# ascender_board.net
KiCad netlist of a schematic drawn in EAGLE
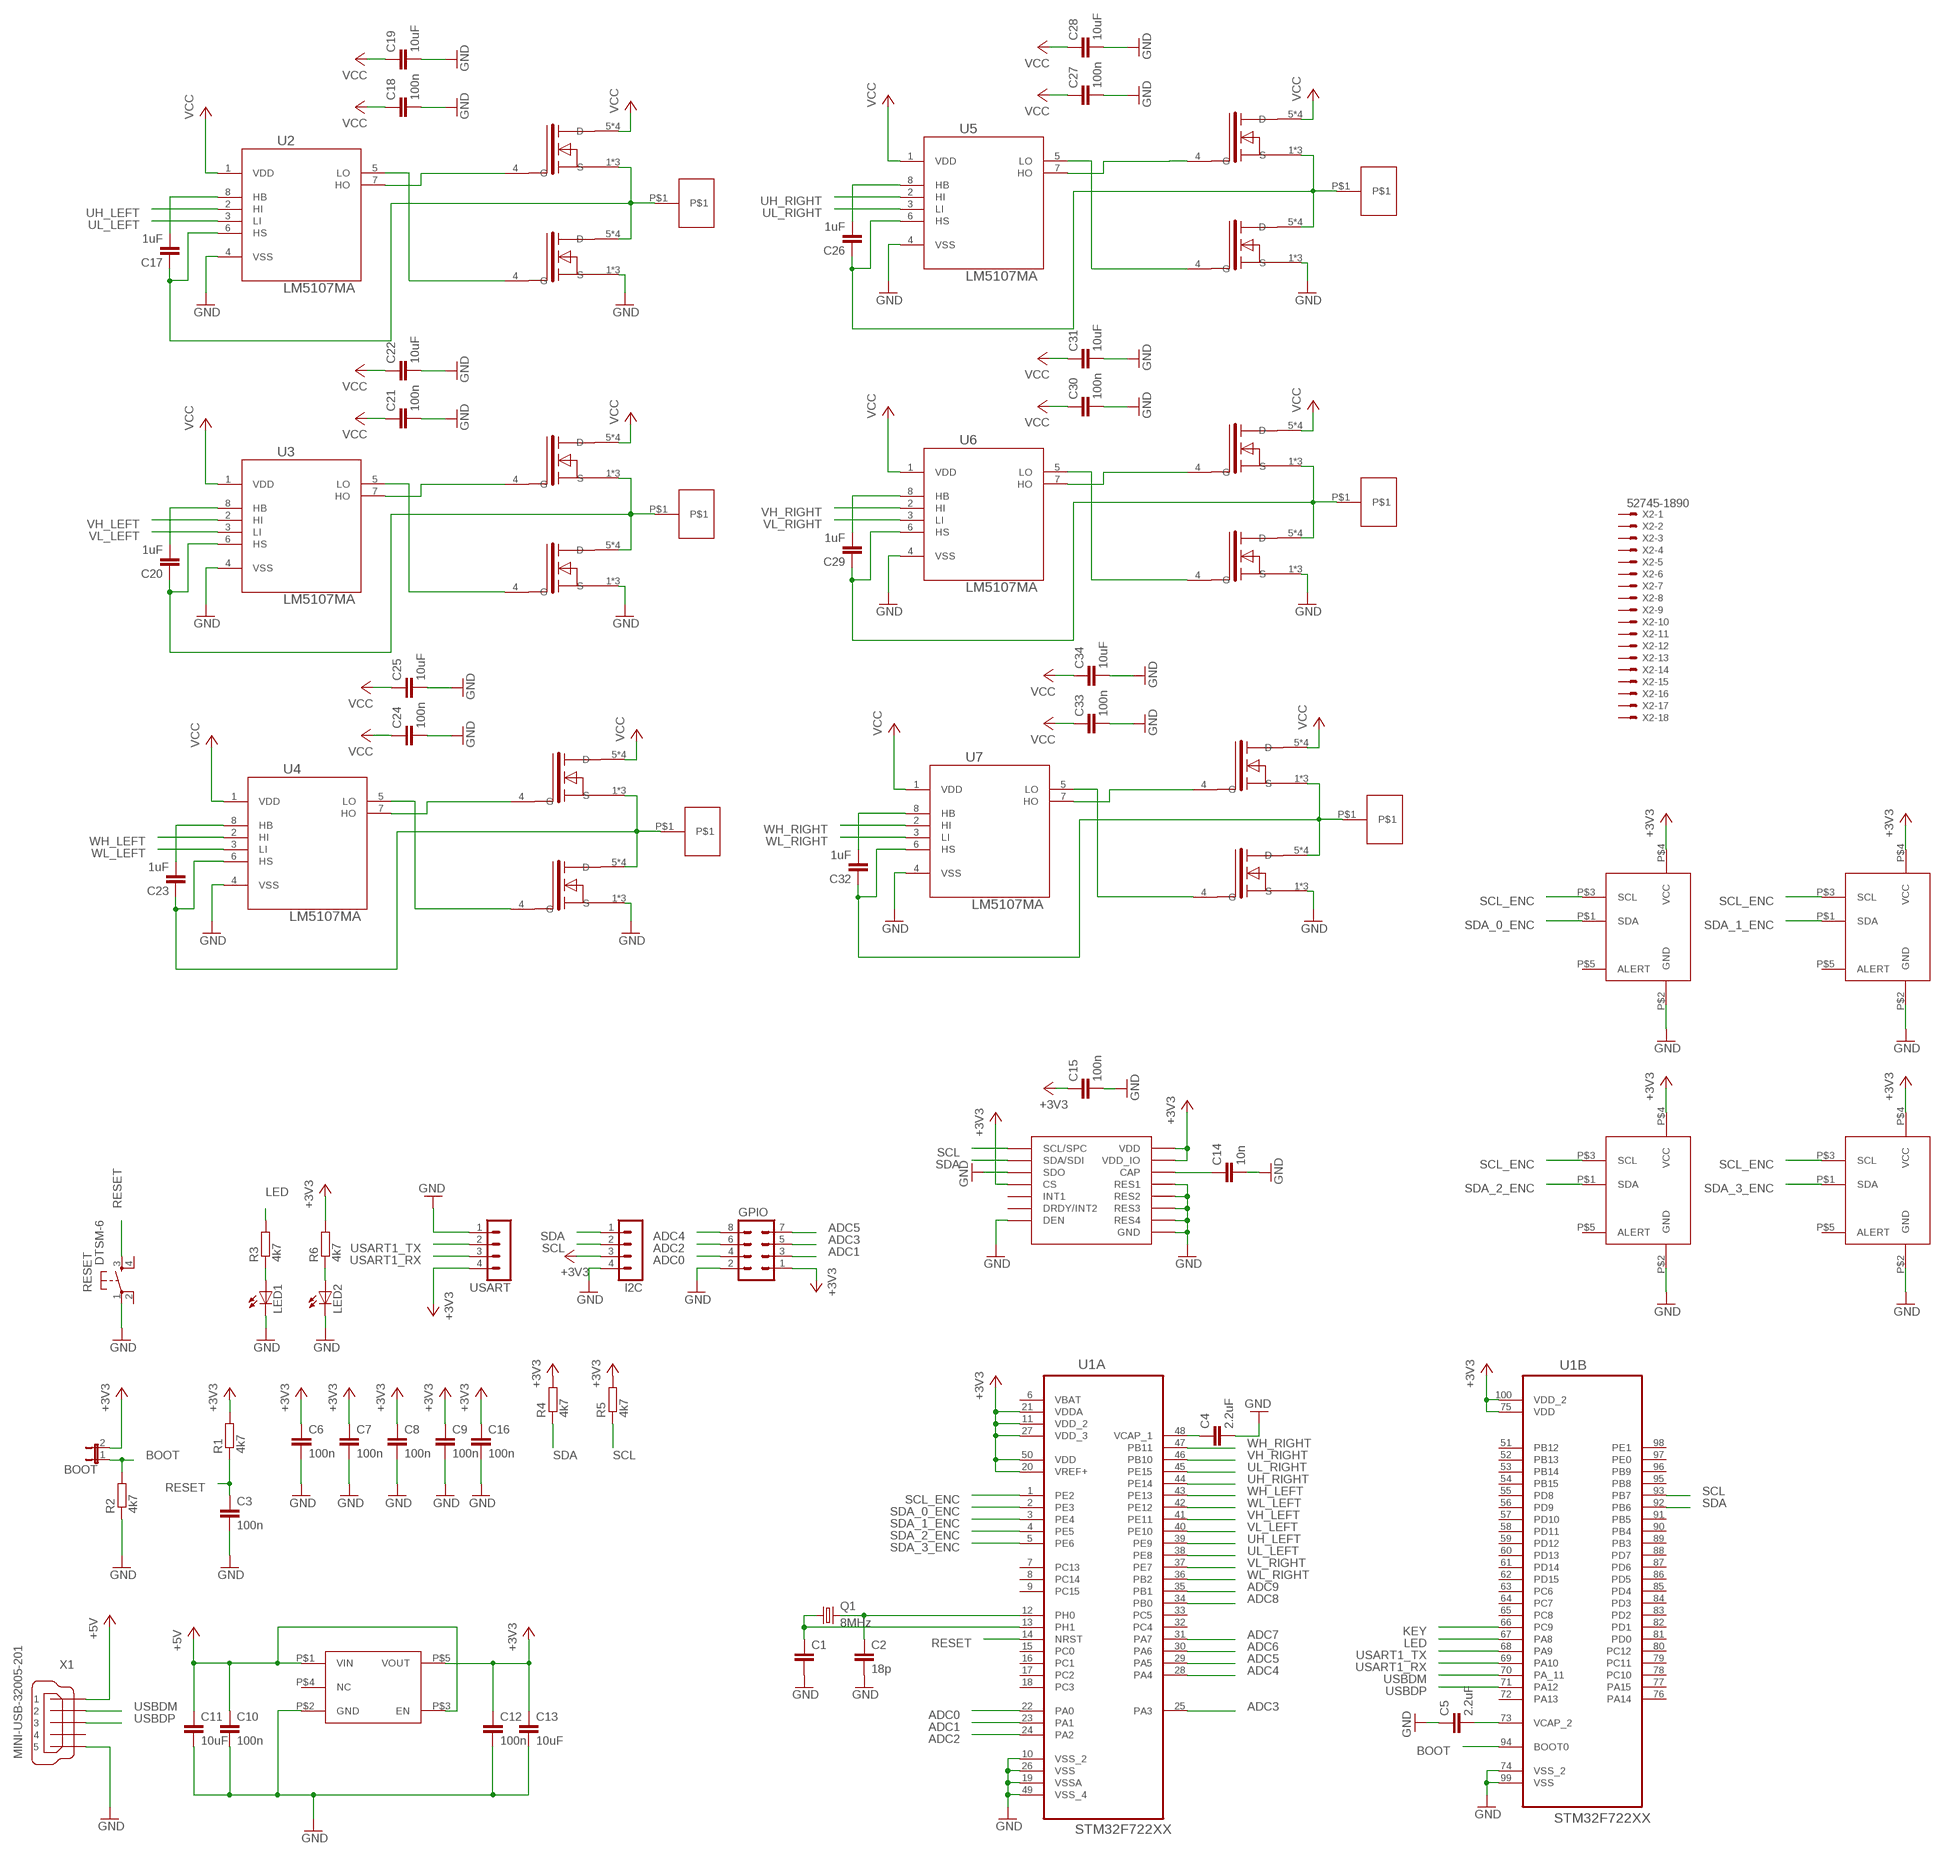
[diagram p0: schematic, sheet 1]

(export (version "E")
  (design (tool "Eeschema 10.0.6"))
  (components
    (comp (ref "BOOT")
      (value "JP1E")
      (footprint "eagle-import:JP1")
      (libsource (lib "eagle-import") (part "JP1E"))
    )
    (comp (ref "C1")
      (value "C-EUC0805")
      (footprint "eagle-import:C0805")
      (libsource (lib "eagle-import") (part "C-EUC0805"))
    )
    (comp (ref "C2")
      (value "18p")
      (footprint "eagle-import:C0805")
      (libsource (lib "eagle-import") (part "C-EUC0805"))
    )
    (comp (ref "C3")
      (value "100n")
      (footprint "eagle-import:C0805")
      (libsource (lib "eagle-import") (part "C-EUC0805"))
    )
    (comp (ref "C4")
      (value "2.2uF")
      (footprint "eagle-import:C0805")
      (libsource (lib "eagle-import") (part "C-EUC0805"))
    )
    (comp (ref "C5")
      (value "2.2uF")
      (footprint "eagle-import:C0805")
      (libsource (lib "eagle-import") (part "C-EUC0805"))
    )
    (comp (ref "C6")
      (value "100n")
      (footprint "eagle-import:C0805")
      (libsource (lib "eagle-import") (part "C-EUC0805"))
    )
    (comp (ref "C7")
      (value "100n")
      (footprint "eagle-import:C0805")
      (libsource (lib "eagle-import") (part "C-EUC0805"))
    )
    (comp (ref "C8")
      (value "100n")
      (footprint "eagle-import:C0805")
      (libsource (lib "eagle-import") (part "C-EUC0805"))
    )
    (comp (ref "C9")
      (value "100n")
      (footprint "eagle-import:C0805")
      (libsource (lib "eagle-import") (part "C-EUC0805"))
    )
    (comp (ref "C10")
      (value "100n")
      (footprint "eagle-import:C0805")
      (libsource (lib "eagle-import") (part "C-EUC0805"))
    )
    (comp (ref "C11")
      (value "10uF")
      (footprint "eagle-import:C0805")
      (libsource (lib "eagle-import") (part "C-EUC0805"))
    )
    (comp (ref "C12")
      (value "100n")
      (footprint "eagle-import:C0805")
      (libsource (lib "eagle-import") (part "C-EUC0805"))
    )
    (comp (ref "C13")
      (value "10uF")
      (footprint "eagle-import:C0805")
      (libsource (lib "eagle-import") (part "C-EUC0805"))
    )
    (comp (ref "C14")
      (value "10n")
      (footprint "eagle-import:C0805")
      (libsource (lib "eagle-import") (part "C-EUC0805"))
    )
    (comp (ref "C15")
      (value "100n")
      (footprint "eagle-import:C0805")
      (libsource (lib "eagle-import") (part "C-EUC0805"))
    )
    (comp (ref "C16")
      (value "100n")
      (footprint "eagle-import:C0805")
      (libsource (lib "eagle-import") (part "C-EUC0805"))
    )
    (comp (ref "C17")
      (value "1uF")
      (footprint "eagle-import:C0805")
      (libsource (lib "eagle-import") (part "C-EUC0805"))
    )
    (comp (ref "C18")
      (value "100n")
      (footprint "eagle-import:C0805")
      (libsource (lib "eagle-import") (part "C-EUC0805"))
    )
    (comp (ref "C19")
      (value "10uF")
      (footprint "eagle-import:C0805")
      (libsource (lib "eagle-import") (part "C-EUC0805"))
    )
    (comp (ref "C20")
      (value "1uF")
      (footprint "eagle-import:C0805")
      (libsource (lib "eagle-import") (part "C-EUC0805"))
    )
    (comp (ref "C21")
      (value "100n")
      (footprint "eagle-import:C0805")
      (libsource (lib "eagle-import") (part "C-EUC0805"))
    )
    (comp (ref "C22")
      (value "10uF")
      (footprint "eagle-import:C0805")
      (libsource (lib "eagle-import") (part "C-EUC0805"))
    )
    (comp (ref "C23")
      (value "1uF")
      (footprint "eagle-import:C0805")
      (libsource (lib "eagle-import") (part "C-EUC0805"))
    )
    (comp (ref "C24")
      (value "100n")
      (footprint "eagle-import:C0805")
      (libsource (lib "eagle-import") (part "C-EUC0805"))
    )
    (comp (ref "C25")
      (value "10uF")
      (footprint "eagle-import:C0805")
      (libsource (lib "eagle-import") (part "C-EUC0805"))
    )
    (comp (ref "C26")
      (value "1uF")
      (footprint "eagle-import:C0805")
      (libsource (lib "eagle-import") (part "C-EUC0805"))
    )
    (comp (ref "C27")
      (value "100n")
      (footprint "eagle-import:C0805")
      (libsource (lib "eagle-import") (part "C-EUC0805"))
    )
    (comp (ref "C28")
      (value "10uF")
      (footprint "eagle-import:C0805")
      (libsource (lib "eagle-import") (part "C-EUC0805"))
    )
    (comp (ref "C29")
      (value "1uF")
      (footprint "eagle-import:C0805")
      (libsource (lib "eagle-import") (part "C-EUC0805"))
    )
    (comp (ref "C30")
      (value "100n")
      (footprint "eagle-import:C0805")
      (libsource (lib "eagle-import") (part "C-EUC0805"))
    )
    (comp (ref "C31")
      (value "10uF")
      (footprint "eagle-import:C0805")
      (libsource (lib "eagle-import") (part "C-EUC0805"))
    )
    (comp (ref "C32")
      (value "1uF")
      (footprint "eagle-import:C0805")
      (libsource (lib "eagle-import") (part "C-EUC0805"))
    )
    (comp (ref "C33")
      (value "100n")
      (footprint "eagle-import:C0805")
      (libsource (lib "eagle-import") (part "C-EUC0805"))
    )
    (comp (ref "C34")
      (value "10uF")
      (footprint "eagle-import:C0805")
      (libsource (lib "eagle-import") (part "C-EUC0805"))
    )
    (comp (ref "GPIO")
      (value "MA04-2")
      (footprint "eagle-import:MA04-2")
      (libsource (lib "eagle-import") (part "MA04-2"))
    )
    (comp (ref "I2C")
      (value "MA04-1")
      (footprint "eagle-import:MA04-1")
      (libsource (lib "eagle-import") (part "MA04-1"))
    )
    (comp (ref "LED1")
      (value "LEDCHIPLED_1206")
      (footprint "eagle-import:CHIPLED_1206")
      (libsource (lib "eagle-import") (part "LEDCHIPLED_1206"))
    )
    (comp (ref "LED2")
      (value "LEDCHIPLED_1206")
      (footprint "eagle-import:CHIPLED_1206")
      (libsource (lib "eagle-import") (part "LEDCHIPLED_1206"))
    )
    (comp (ref "Q1")
      (value "8MHz")
      (footprint "eagle-import:CTS406")
      (libsource (lib "eagle-import") (part "CRYSTALCTS406"))
    )
    (comp (ref "R1")
      (value "4k7")
      (footprint "eagle-import:M0805")
      (libsource (lib "eagle-import") (part "R-EU_M0805"))
    )
    (comp (ref "R2")
      (value "4k7")
      (footprint "eagle-import:M0805")
      (libsource (lib "eagle-import") (part "R-EU_M0805"))
    )
    (comp (ref "R3")
      (value "4k7")
      (footprint "eagle-import:M0805")
      (libsource (lib "eagle-import") (part "R-EU_M0805"))
    )
    (comp (ref "R4")
      (value "4k7")
      (footprint "eagle-import:M0805")
      (libsource (lib "eagle-import") (part "R-EU_M0805"))
    )
    (comp (ref "R5")
      (value "4k7")
      (footprint "eagle-import:M0805")
      (libsource (lib "eagle-import") (part "R-EU_M0805"))
    )
    (comp (ref "R6")
      (value "4k7")
      (footprint "eagle-import:M0805")
      (libsource (lib "eagle-import") (part "R-EU_M0805"))
    )
    (comp (ref "RESET")
      (value "DTSM-6")
      (footprint "eagle-import:DTSM-6")
      (libsource (lib "eagle-import") (part "DTSM-6"))
    )
    (comp (ref "U$1")
      (value "MIC5504-3.3Y")
      (footprint "eagle-import:SOT23-5")
      (libsource (lib "eagle-import") (part "MIC5504-3.3Y"))
    )
    (comp (ref "U$2")
      (value "ST_L3GD20H")
      (footprint "eagle-import:ST_LGA16L")
      (libsource (lib "eagle-import") (part "ST_L3GD20H"))
    )
    (comp (ref "U$4")
      (value "IRFH7004")
      (footprint "eagle-import:PQFN5X6")
      (libsource (lib "eagle-import") (part "IRFH7004"))
    )
    (comp (ref "U$5")
      (value "IRFH7004")
      (footprint "eagle-import:PQFN5X6")
      (libsource (lib "eagle-import") (part "IRFH7004"))
    )
    (comp (ref "U$6")
      (value "BLDC_MOTOR_PIN")
      (footprint "eagle-import:BLDC_MOTOR_PIN")
      (libsource (lib "eagle-import") (part "BLDC_MOTOR_PIN"))
    )
    (comp (ref "U$7")
      (value "IRFH7004")
      (footprint "eagle-import:PQFN5X6")
      (libsource (lib "eagle-import") (part "IRFH7004"))
    )
    (comp (ref "U$8")
      (value "IRFH7004")
      (footprint "eagle-import:PQFN5X6")
      (libsource (lib "eagle-import") (part "IRFH7004"))
    )
    (comp (ref "U$9")
      (value "BLDC_MOTOR_PIN")
      (footprint "eagle-import:BLDC_MOTOR_PIN")
      (libsource (lib "eagle-import") (part "BLDC_MOTOR_PIN"))
    )
    (comp (ref "U$10")
      (value "IRFH7004")
      (footprint "eagle-import:PQFN5X6")
      (libsource (lib "eagle-import") (part "IRFH7004"))
    )
    (comp (ref "U$11")
      (value "IRFH7004")
      (footprint "eagle-import:PQFN5X6")
      (libsource (lib "eagle-import") (part "IRFH7004"))
    )
    (comp (ref "U$12")
      (value "BLDC_MOTOR_PIN")
      (footprint "eagle-import:BLDC_MOTOR_PIN")
      (libsource (lib "eagle-import") (part "BLDC_MOTOR_PIN"))
    )
    (comp (ref "U$13")
      (value "IRFH7004")
      (footprint "eagle-import:PQFN5X6")
      (libsource (lib "eagle-import") (part "IRFH7004"))
    )
    (comp (ref "U$14")
      (value "IRFH7004")
      (footprint "eagle-import:PQFN5X6")
      (libsource (lib "eagle-import") (part "IRFH7004"))
    )
    (comp (ref "U$15")
      (value "BLDC_MOTOR_PIN")
      (footprint "eagle-import:BLDC_MOTOR_PIN")
      (libsource (lib "eagle-import") (part "BLDC_MOTOR_PIN"))
    )
    (comp (ref "U$16")
      (value "IRFH7004")
      (footprint "eagle-import:PQFN5X6")
      (libsource (lib "eagle-import") (part "IRFH7004"))
    )
    (comp (ref "U$17")
      (value "IRFH7004")
      (footprint "eagle-import:PQFN5X6")
      (libsource (lib "eagle-import") (part "IRFH7004"))
    )
    (comp (ref "U$18")
      (value "BLDC_MOTOR_PIN")
      (footprint "eagle-import:BLDC_MOTOR_PIN")
      (libsource (lib "eagle-import") (part "BLDC_MOTOR_PIN"))
    )
    (comp (ref "U$19")
      (value "IRFH7004")
      (footprint "eagle-import:PQFN5X6")
      (libsource (lib "eagle-import") (part "IRFH7004"))
    )
    (comp (ref "U$20")
      (value "IRFH7004")
      (footprint "eagle-import:PQFN5X6")
      (libsource (lib "eagle-import") (part "IRFH7004"))
    )
    (comp (ref "U$21")
      (value "BLDC_MOTOR_PIN")
      (footprint "eagle-import:BLDC_MOTOR_PIN")
      (libsource (lib "eagle-import") (part "BLDC_MOTOR_PIN"))
    )
    (comp (ref "U$22")
      (value "SI7210")
      (footprint "eagle-import:SOT23-5")
      (libsource (lib "eagle-import") (part "SI7210"))
    )
    (comp (ref "U$23")
      (value "SI7210")
      (footprint "eagle-import:SOT23-5")
      (libsource (lib "eagle-import") (part "SI7210"))
    )
    (comp (ref "U$24")
      (value "SI7210")
      (footprint "eagle-import:SOT23-5")
      (libsource (lib "eagle-import") (part "SI7210"))
    )
    (comp (ref "U$25")
      (value "SI7210")
      (footprint "eagle-import:SOT23-5")
      (libsource (lib "eagle-import") (part "SI7210"))
    )
    (comp (ref "U1")
      (value "STM32F722XX")
      (footprint "eagle-import:QFP50P1600X1600X160-100N")
      (fields (field (name "MPN") "STM32F407VET6"))
      (libsource (lib "eagle-import") (part "STM32F722XX"))
    )
    (comp (ref "U2")
      (value "LM5107MA")
      (footprint "eagle-import:SOIC127P620X175-8N")
      (libsource (lib "eagle-import") (part "LM5107MA"))
    )
    (comp (ref "U3")
      (value "LM5107MA")
      (footprint "eagle-import:SOIC127P620X175-8N")
      (libsource (lib "eagle-import") (part "LM5107MA"))
    )
    (comp (ref "U4")
      (value "LM5107MA")
      (footprint "eagle-import:SOIC127P620X175-8N")
      (libsource (lib "eagle-import") (part "LM5107MA"))
    )
    (comp (ref "U5")
      (value "LM5107MA")
      (footprint "eagle-import:SOIC127P620X175-8N")
      (libsource (lib "eagle-import") (part "LM5107MA"))
    )
    (comp (ref "U6")
      (value "LM5107MA")
      (footprint "eagle-import:SOIC127P620X175-8N")
      (libsource (lib "eagle-import") (part "LM5107MA"))
    )
    (comp (ref "U7")
      (value "LM5107MA")
      (footprint "eagle-import:SOIC127P620X175-8N")
      (libsource (lib "eagle-import") (part "LM5107MA"))
    )
    (comp (ref "USART")
      (value "MA04-1")
      (footprint "eagle-import:MA04-1")
      (libsource (lib "eagle-import") (part "MA04-1"))
    )
    (comp (ref "X1")
      (value "MINI-USB-32005-201")
      (footprint "eagle-import:32005-201")
      (libsource (lib "eagle-import") (part "MINI-USB-32005-201"))
    )
    (comp (ref "X2")
      (value "52745-1890")
      (footprint "eagle-import:52745-1890")
      (libsource (lib "eagle-import") (part "52745-1890"))
    )
  )
  (nets
    (net (code "1") (name "+3V3") (class "Default")
      (node (ref "BOOT") (pin "2") (pinfunction "2_2") (pintype "passive"))
      (node (ref "C12") (pin "1") (pinfunction "1_1") (pintype "passive"))
      (node (ref "C13") (pin "1") (pinfunction "1_1") (pintype "passive"))
      (node (ref "C15") (pin "1") (pinfunction "1_1") (pintype "passive"))
      (node (ref "C16") (pin "1") (pinfunction "1_1") (pintype "passive"))
      (node (ref "C6") (pin "1") (pinfunction "1_1") (pintype "passive"))
      (node (ref "C7") (pin "1") (pinfunction "1_1") (pintype "passive"))
      (node (ref "C8") (pin "1") (pinfunction "1_1") (pintype "passive"))
      (node (ref "C9") (pin "1") (pinfunction "1_1") (pintype "passive"))
      (node (ref "GPIO") (pin "1") (pinfunction "1_1") (pintype "passive"))
      (node (ref "I2C") (pin "3") (pinfunction "3_3") (pintype "passive"))
      (node (ref "R1") (pin "2") (pinfunction "2_2") (pintype "passive"))
      (node (ref "R4") (pin "2") (pinfunction "2_2") (pintype "passive"))
      (node (ref "R5") (pin "2") (pinfunction "2_2") (pintype "passive"))
      (node (ref "R6") (pin "2") (pinfunction "2_2") (pintype "passive"))
      (node (ref "U$1") (pin "P$5") (pinfunction "VOUT_P$5") (pintype "bidirectional"))
      (node (ref "U$2") (pin "P$1") (pinfunction "VDD_IO_P$1") (pintype "power_in"))
      (node (ref "U$2") (pin "P$16") (pinfunction "VDD_P$16") (pintype "power_in"))
      (node (ref "U$2") (pin "P$5") (pinfunction "CS_P$5") (pintype "bidirectional"))
      (node (ref "U$22") (pin "P$4") (pinfunction "VCC_P$4") (pintype "bidirectional"))
      (node (ref "U$23") (pin "P$4") (pinfunction "VCC_P$4") (pintype "bidirectional"))
      (node (ref "U$24") (pin "P$4") (pinfunction "VCC_P$4") (pintype "bidirectional"))
      (node (ref "U$25") (pin "P$4") (pinfunction "VCC_P$4") (pintype "bidirectional"))
      (node (ref "U1") (pin "100") (pinfunction "VDD_2_100") (pintype "power_in"))
      (node (ref "U1") (pin "11") (pinfunction "VDD_2_11") (pintype "power_in"))
      (node (ref "U1") (pin "20") (pinfunction "VREF+_20") (pintype "power_in"))
      (node (ref "U1") (pin "21") (pinfunction "VDDA_21") (pintype "power_in"))
      (node (ref "U1") (pin "27") (pinfunction "VDD_3_27") (pintype "power_in"))
      (node (ref "U1") (pin "50") (pinfunction "VDD_50") (pintype "power_in"))
      (node (ref "U1") (pin "75") (pinfunction "VDD_75") (pintype "power_in"))
      (node (ref "USART") (pin "4") (pinfunction "4_4") (pintype "passive"))
    )
    (net (code "2") (name "+5V") (class "Default")
      (node (ref "C10") (pin "1") (pinfunction "1_1") (pintype "passive"))
      (node (ref "C11") (pin "1") (pinfunction "1_1") (pintype "passive"))
      (node (ref "U$1") (pin "P$1") (pinfunction "VIN_P$1") (pintype "bidirectional"))
      (node (ref "U$1") (pin "P$3") (pinfunction "EN_P$3") (pintype "bidirectional"))
      (node (ref "X1") (pin "1") (pinfunction "1_1") (pintype "passive"))
    )
    (net (code "3") (name "/ADC0") (class "Default")
      (node (ref "GPIO") (pin "4") (pinfunction "4_4") (pintype "passive"))
      (node (ref "U1") (pin "22") (pinfunction "PA0_22") (pintype "bidirectional"))
    )
    (net (code "4") (name "/ADC1") (class "Default")
      (node (ref "GPIO") (pin "3") (pinfunction "3_3") (pintype "passive"))
      (node (ref "U1") (pin "23") (pinfunction "PA1_23") (pintype "bidirectional"))
    )
    (net (code "5") (name "/ADC2") (class "Default")
      (node (ref "GPIO") (pin "6") (pinfunction "6_6") (pintype "passive"))
      (node (ref "U1") (pin "24") (pinfunction "PA2_24") (pintype "bidirectional"))
    )
    (net (code "6") (name "/ADC3") (class "Default")
      (node (ref "GPIO") (pin "5") (pinfunction "5_5") (pintype "passive"))
      (node (ref "U1") (pin "25") (pinfunction "PA3_25") (pintype "bidirectional"))
    )
    (net (code "7") (name "/ADC4") (class "Default")
      (node (ref "GPIO") (pin "8") (pinfunction "8_8") (pintype "passive"))
      (node (ref "U1") (pin "28") (pinfunction "PA4_28") (pintype "bidirectional"))
    )
    (net (code "8") (name "/ADC5") (class "Default")
      (node (ref "GPIO") (pin "7") (pinfunction "7_7") (pintype "passive"))
      (node (ref "U1") (pin "29") (pinfunction "PA5_29") (pintype "bidirectional"))
    )
    (net (code "9") (name "/ADC6") (class "Default")
      (node (ref "U1") (pin "30") (pinfunction "PA6_30") (pintype "bidirectional"))
    )
    (net (code "10") (name "/ADC7") (class "Default")
      (node (ref "U1") (pin "31") (pinfunction "PA7_31") (pintype "bidirectional"))
    )
    (net (code "11") (name "/ADC8") (class "Default")
      (node (ref "U1") (pin "34") (pinfunction "PB0_34") (pintype "bidirectional"))
    )
    (net (code "12") (name "/ADC9") (class "Default")
      (node (ref "U1") (pin "35") (pinfunction "PB1_35") (pintype "bidirectional"))
    )
    (net (code "13") (name "/BOOT") (class "Default")
      (node (ref "BOOT") (pin "1") (pinfunction "1_1") (pintype "passive"))
      (node (ref "R2") (pin "2") (pinfunction "2_2") (pintype "passive"))
      (node (ref "U1") (pin "94") (pinfunction "BOOT0_94") (pintype "input"))
    )
    (net (code "14") (name "/KEY") (class "Default")
      (node (ref "U1") (pin "66") (pinfunction "PC9_66") (pintype "bidirectional"))
    )
    (net (code "15") (name "/LED") (class "Default")
      (node (ref "R3") (pin "2") (pinfunction "2_2") (pintype "passive"))
      (node (ref "U1") (pin "67") (pinfunction "PA8_67") (pintype "bidirectional"))
    )
    (net (code "16") (name "/RESET") (class "Default")
      (node (ref "C3") (pin "1") (pinfunction "1_1") (pintype "passive"))
      (node (ref "R1") (pin "1") (pinfunction "1_1") (pintype "passive"))
      (node (ref "RESET") (pin "3") (pinfunction "3_3") (pintype "passive"))
      (node (ref "U1") (pin "14") (pinfunction "NRST_14") (pintype "bidirectional"))
    )
    (net (code "17") (name "/SCL") (class "Default")
      (node (ref "I2C") (pin "2") (pinfunction "2_2") (pintype "passive"))
      (node (ref "R5") (pin "1") (pinfunction "1_1") (pintype "passive"))
      (node (ref "U$2") (pin "P$2") (pinfunction "SCL/SPC_P$2") (pintype "bidirectional"))
      (node (ref "U1") (pin "93") (pinfunction "PB7_93") (pintype "bidirectional"))
    )
    (net (code "18") (name "/SCL_ENC") (class "Default")
      (node (ref "U$22") (pin "P$3") (pinfunction "SCL_P$3") (pintype "bidirectional"))
      (node (ref "U$23") (pin "P$3") (pinfunction "SCL_P$3") (pintype "bidirectional"))
      (node (ref "U$24") (pin "P$3") (pinfunction "SCL_P$3") (pintype "bidirectional"))
      (node (ref "U$25") (pin "P$3") (pinfunction "SCL_P$3") (pintype "bidirectional"))
      (node (ref "U1") (pin "1") (pinfunction "PE2_1") (pintype "bidirectional"))
    )
    (net (code "19") (name "/SDA") (class "Default")
      (node (ref "I2C") (pin "1") (pinfunction "1_1") (pintype "passive"))
      (node (ref "R4") (pin "1") (pinfunction "1_1") (pintype "passive"))
      (node (ref "U$2") (pin "P$3") (pinfunction "SDA/SDI_P$3") (pintype "bidirectional"))
      (node (ref "U1") (pin "92") (pinfunction "PB6_92") (pintype "bidirectional"))
    )
    (net (code "20") (name "/SDA_0_ENC") (class "Default")
      (node (ref "U$22") (pin "P$1") (pinfunction "SDA_P$1") (pintype "bidirectional"))
      (node (ref "U1") (pin "2") (pinfunction "PE3_2") (pintype "bidirectional"))
    )
    (net (code "21") (name "/SDA_1_ENC") (class "Default")
      (node (ref "U$23") (pin "P$1") (pinfunction "SDA_P$1") (pintype "bidirectional"))
      (node (ref "U1") (pin "3") (pinfunction "PE4_3") (pintype "bidirectional"))
    )
    (net (code "22") (name "/SDA_2_ENC") (class "Default")
      (node (ref "U$24") (pin "P$1") (pinfunction "SDA_P$1") (pintype "bidirectional"))
      (node (ref "U1") (pin "4") (pinfunction "PE5_4") (pintype "bidirectional"))
    )
    (net (code "23") (name "/SDA_3_ENC") (class "Default")
      (node (ref "U$25") (pin "P$1") (pinfunction "SDA_P$1") (pintype "bidirectional"))
      (node (ref "U1") (pin "5") (pinfunction "PE6_5") (pintype "bidirectional"))
    )
    (net (code "24") (name "/UH_LEFT") (class "Default")
      (node (ref "U1") (pin "39") (pinfunction "PE9_39") (pintype "bidirectional"))
      (node (ref "U2") (pin "2") (pinfunction "HI_2") (pintype "input"))
    )
    (net (code "25") (name "/UH_RIGHT") (class "Default")
      (node (ref "U1") (pin "44") (pinfunction "PE14_44") (pintype "bidirectional"))
      (node (ref "U5") (pin "2") (pinfunction "HI_2") (pintype "input"))
    )
    (net (code "26") (name "/UL_LEFT") (class "Default")
      (node (ref "U1") (pin "38") (pinfunction "PE8_38") (pintype "bidirectional"))
      (node (ref "U2") (pin "3") (pinfunction "LI_3") (pintype "input"))
    )
    (net (code "27") (name "/UL_RIGHT") (class "Default")
      (node (ref "U1") (pin "45") (pinfunction "PE15_45") (pintype "bidirectional"))
      (node (ref "U5") (pin "3") (pinfunction "LI_3") (pintype "input"))
    )
    (net (code "28") (name "/USART1_RX") (class "Default")
      (node (ref "U1") (pin "69") (pinfunction "PA10_69") (pintype "bidirectional"))
      (node (ref "USART") (pin "3") (pinfunction "3_3") (pintype "passive"))
    )
    (net (code "29") (name "/USART1_TX") (class "Default")
      (node (ref "U1") (pin "68") (pinfunction "PA9_68") (pintype "bidirectional"))
      (node (ref "USART") (pin "2") (pinfunction "2_2") (pintype "passive"))
    )
    (net (code "30") (name "/USBDM") (class "Default")
      (node (ref "U1") (pin "70") (pinfunction "PA_11_70") (pintype "bidirectional"))
      (node (ref "X1") (pin "2") (pinfunction "2_2") (pintype "passive"))
    )
    (net (code "31") (name "/USBDP") (class "Default")
      (node (ref "U1") (pin "71") (pinfunction "PA12_71") (pintype "bidirectional"))
      (node (ref "X1") (pin "3") (pinfunction "3_3") (pintype "passive"))
    )
    (net (code "32") (name "/VBAT") (class "Default")
      (node (ref "U1") (pin "6") (pinfunction "VBAT_6") (pintype "power_in"))
    )
    (net (code "33") (name "/VH_LEFT") (class "Default")
      (node (ref "U1") (pin "41") (pinfunction "PE11_41") (pintype "bidirectional"))
      (node (ref "U3") (pin "2") (pinfunction "HI_2") (pintype "input"))
    )
    (net (code "34") (name "/VH_RIGHT") (class "Default")
      (node (ref "U1") (pin "46") (pinfunction "PB10_46") (pintype "bidirectional"))
      (node (ref "U6") (pin "2") (pinfunction "HI_2") (pintype "input"))
    )
    (net (code "35") (name "/VL_LEFT") (class "Default")
      (node (ref "U1") (pin "40") (pinfunction "PE10_40") (pintype "bidirectional"))
      (node (ref "U3") (pin "3") (pinfunction "LI_3") (pintype "input"))
    )
    (net (code "36") (name "/VL_RIGHT") (class "Default")
      (node (ref "U1") (pin "37") (pinfunction "PE7_37") (pintype "bidirectional"))
      (node (ref "U6") (pin "3") (pinfunction "LI_3") (pintype "input"))
    )
    (net (code "37") (name "/WH_LEFT") (class "Default")
      (node (ref "U1") (pin "43") (pinfunction "PE13_43") (pintype "bidirectional"))
      (node (ref "U4") (pin "2") (pinfunction "HI_2") (pintype "input"))
    )
    (net (code "38") (name "/WH_RIGHT") (class "Default")
      (node (ref "U1") (pin "47") (pinfunction "PB11_47") (pintype "bidirectional"))
      (node (ref "U7") (pin "2") (pinfunction "HI_2") (pintype "input"))
    )
    (net (code "39") (name "/WL_LEFT") (class "Default")
      (node (ref "U1") (pin "42") (pinfunction "PE12_42") (pintype "bidirectional"))
      (node (ref "U4") (pin "3") (pinfunction "LI_3") (pintype "input"))
    )
    (net (code "40") (name "/WL_RIGHT") (class "Default")
      (node (ref "U1") (pin "36") (pinfunction "PB2_36") (pintype "bidirectional"))
      (node (ref "U7") (pin "3") (pinfunction "LI_3") (pintype "input"))
    )
    (net (code "41") (name "GND") (class "Default")
      (node (ref "C1") (pin "2") (pinfunction "2_2") (pintype "passive"))
      (node (ref "C10") (pin "2") (pinfunction "2_2") (pintype "passive"))
      (node (ref "C11") (pin "2") (pinfunction "2_2") (pintype "passive"))
      (node (ref "C12") (pin "2") (pinfunction "2_2") (pintype "passive"))
      (node (ref "C13") (pin "2") (pinfunction "2_2") (pintype "passive"))
      (node (ref "C14") (pin "2") (pinfunction "2_2") (pintype "passive"))
      (node (ref "C15") (pin "2") (pinfunction "2_2") (pintype "passive"))
      (node (ref "C16") (pin "2") (pinfunction "2_2") (pintype "passive"))
      (node (ref "C18") (pin "2") (pinfunction "2_2") (pintype "passive"))
      (node (ref "C19") (pin "2") (pinfunction "2_2") (pintype "passive"))
      (node (ref "C2") (pin "2") (pinfunction "2_2") (pintype "passive"))
      (node (ref "C21") (pin "2") (pinfunction "2_2") (pintype "passive"))
      (node (ref "C22") (pin "2") (pinfunction "2_2") (pintype "passive"))
      (node (ref "C24") (pin "2") (pinfunction "2_2") (pintype "passive"))
      (node (ref "C25") (pin "2") (pinfunction "2_2") (pintype "passive"))
      (node (ref "C27") (pin "2") (pinfunction "2_2") (pintype "passive"))
      (node (ref "C28") (pin "2") (pinfunction "2_2") (pintype "passive"))
      (node (ref "C3") (pin "2") (pinfunction "2_2") (pintype "passive"))
      (node (ref "C30") (pin "2") (pinfunction "2_2") (pintype "passive"))
      (node (ref "C31") (pin "2") (pinfunction "2_2") (pintype "passive"))
      (node (ref "C33") (pin "2") (pinfunction "2_2") (pintype "passive"))
      (node (ref "C34") (pin "2") (pinfunction "2_2") (pintype "passive"))
      (node (ref "C4") (pin "2") (pinfunction "2_2") (pintype "passive"))
      (node (ref "C5") (pin "1") (pinfunction "1_1") (pintype "passive"))
      (node (ref "C6") (pin "2") (pinfunction "2_2") (pintype "passive"))
      (node (ref "C7") (pin "2") (pinfunction "2_2") (pintype "passive"))
      (node (ref "C8") (pin "2") (pinfunction "2_2") (pintype "passive"))
      (node (ref "C9") (pin "2") (pinfunction "2_2") (pintype "passive"))
      (node (ref "GPIO") (pin "2") (pinfunction "2_2") (pintype "passive"))
      (node (ref "I2C") (pin "4") (pinfunction "4_4") (pintype "passive"))
      (node (ref "LED1") (pin "C") (pinfunction "C_C") (pintype "passive"))
      (node (ref "LED2") (pin "C") (pinfunction "C_C") (pintype "passive"))
      (node (ref "R2") (pin "1") (pinfunction "1_1") (pintype "passive"))
      (node (ref "RESET") (pin "1") (pinfunction "1_1") (pintype "passive"))
      (node (ref "U$1") (pin "P$2") (pinfunction "GND_P$2") (pintype "bidirectional"))
      (node (ref "U$11") (pin "1") (pinfunction "S_1") (pintype "bidirectional"))
      (node (ref "U$11") (pin "2") (pinfunction "S_2") (pintype "bidirectional"))
      (node (ref "U$11") (pin "3") (pinfunction "S_3") (pintype "bidirectional"))
      (node (ref "U$14") (pin "1") (pinfunction "S_1") (pintype "bidirectional"))
      (node (ref "U$14") (pin "2") (pinfunction "S_2") (pintype "bidirectional"))
      (node (ref "U$14") (pin "3") (pinfunction "S_3") (pintype "bidirectional"))
      (node (ref "U$17") (pin "1") (pinfunction "S_1") (pintype "bidirectional"))
      (node (ref "U$17") (pin "2") (pinfunction "S_2") (pintype "bidirectional"))
      (node (ref "U$17") (pin "3") (pinfunction "S_3") (pintype "bidirectional"))
      (node (ref "U$2") (pin "P$10") (pinfunction "RES2_P$10") (pintype "bidirectional"))
      (node (ref "U$2") (pin "P$11") (pinfunction "RES3_P$11") (pintype "bidirectional"))
      (node (ref "U$2") (pin "P$12") (pinfunction "GND_P$12") (pintype "power_in"))
      (node (ref "U$2") (pin "P$13") (pinfunction "GND_P$13") (pintype "power_in"))
      (node (ref "U$2") (pin "P$15") (pinfunction "RES4_P$15") (pintype "bidirectional"))
      (node (ref "U$2") (pin "P$4") (pinfunction "SDO_P$4") (pintype "bidirectional"))
      (node (ref "U$2") (pin "P$8") (pinfunction "DEN_P$8") (pintype "bidirectional"))
      (node (ref "U$2") (pin "P$9") (pinfunction "RES1_P$9") (pintype "bidirectional"))
      (node (ref "U$20") (pin "1") (pinfunction "S_1") (pintype "bidirectional"))
      (node (ref "U$20") (pin "2") (pinfunction "S_2") (pintype "bidirectional"))
      (node (ref "U$20") (pin "3") (pinfunction "S_3") (pintype "bidirectional"))
      (node (ref "U$22") (pin "P$2") (pinfunction "GND_P$2") (pintype "bidirectional"))
      (node (ref "U$23") (pin "P$2") (pinfunction "GND_P$2") (pintype "bidirectional"))
      (node (ref "U$24") (pin "P$2") (pinfunction "GND_P$2") (pintype "bidirectional"))
      (node (ref "U$25") (pin "P$2") (pinfunction "GND_P$2") (pintype "bidirectional"))
      (node (ref "U$5") (pin "1") (pinfunction "S_1") (pintype "bidirectional"))
      (node (ref "U$5") (pin "2") (pinfunction "S_2") (pintype "bidirectional"))
      (node (ref "U$5") (pin "3") (pinfunction "S_3") (pintype "bidirectional"))
      (node (ref "U$8") (pin "1") (pinfunction "S_1") (pintype "bidirectional"))
      (node (ref "U$8") (pin "2") (pinfunction "S_2") (pintype "bidirectional"))
      (node (ref "U$8") (pin "3") (pinfunction "S_3") (pintype "bidirectional"))
      (node (ref "U1") (pin "10") (pinfunction "VSS_2_10") (pintype "passive"))
      (node (ref "U1") (pin "19") (pinfunction "VSSA_19") (pintype "passive"))
      (node (ref "U1") (pin "26") (pinfunction "VSS_26") (pintype "passive"))
      (node (ref "U1") (pin "49") (pinfunction "VSS_4_49") (pintype "power_in"))
      (node (ref "U1") (pin "74") (pinfunction "VSS_2_74") (pintype "passive"))
      (node (ref "U1") (pin "99") (pinfunction "VSS_99") (pintype "passive"))
      (node (ref "U2") (pin "4") (pinfunction "VSS_4") (pintype "power_in"))
      (node (ref "U3") (pin "4") (pinfunction "VSS_4") (pintype "power_in"))
      (node (ref "U4") (pin "4") (pinfunction "VSS_4") (pintype "power_in"))
      (node (ref "U5") (pin "4") (pinfunction "VSS_4") (pintype "power_in"))
      (node (ref "U6") (pin "4") (pinfunction "VSS_4") (pintype "power_in"))
      (node (ref "U7") (pin "4") (pinfunction "VSS_4") (pintype "power_in"))
      (node (ref "USART") (pin "1") (pinfunction "1_1") (pintype "passive"))
      (node (ref "X1") (pin "5") (pinfunction "5_5") (pintype "passive"))
    )
    (net (code "42") (name "Net-(LED1-PadA)") (class "Default")
      (node (ref "LED1") (pin "A") (pinfunction "A_A") (pintype "passive"))
      (node (ref "R3") (pin "1") (pinfunction "1_1") (pintype "passive"))
    )
    (net (code "43") (name "Net-(LED2-PadA)") (class "Default")
      (node (ref "LED2") (pin "A") (pinfunction "A_A") (pintype "passive"))
      (node (ref "R6") (pin "1") (pinfunction "1_1") (pintype "passive"))
    )
    (net (code "44") (name "Net-(Q1-2)") (class "Default")
      (node (ref "C2") (pin "1") (pinfunction "1_1") (pintype "passive"))
      (node (ref "Q1") (pin "3") (pinfunction "2_3") (pintype "passive"))
      (node (ref "U1") (pin "12") (pinfunction "PH0_12") (pintype "bidirectional"))
    )
    (net (code "45") (name "Net-(U$2-CAP)") (class "Default")
      (node (ref "C14") (pin "1") (pinfunction "1_1") (pintype "passive"))
      (node (ref "U$2") (pin "P$14") (pinfunction "CAP_P$14") (pintype "bidirectional"))
    )
    (net (code "46") (name "Net-(U$4-G)") (class "Default")
      (node (ref "U$4") (pin "4") (pinfunction "G_4") (pintype "bidirectional"))
      (node (ref "U2") (pin "7") (pinfunction "HO_7") (pintype "output"))
    )
    (net (code "47") (name "Net-(U$5-G)") (class "Default")
      (node (ref "U$5") (pin "4") (pinfunction "G_4") (pintype "bidirectional"))
      (node (ref "U2") (pin "5") (pinfunction "LO_5") (pintype "output"))
    )
    (net (code "48") (name "Net-(U$7-G)") (class "Default")
      (node (ref "U$7") (pin "4") (pinfunction "G_4") (pintype "bidirectional"))
      (node (ref "U3") (pin "7") (pinfunction "HO_7") (pintype "output"))
    )
    (net (code "49") (name "Net-(U$8-G)") (class "Default")
      (node (ref "U$8") (pin "4") (pinfunction "G_4") (pintype "bidirectional"))
      (node (ref "U3") (pin "5") (pinfunction "LO_5") (pintype "output"))
    )
    (net (code "50") (name "Net-(U$10-G)") (class "Default")
      (node (ref "U$10") (pin "4") (pinfunction "G_4") (pintype "bidirectional"))
      (node (ref "U4") (pin "7") (pinfunction "HO_7") (pintype "output"))
    )
    (net (code "51") (name "Net-(U$11-G)") (class "Default")
      (node (ref "U$11") (pin "4") (pinfunction "G_4") (pintype "bidirectional"))
      (node (ref "U4") (pin "5") (pinfunction "LO_5") (pintype "output"))
    )
    (net (code "52") (name "Net-(U$13-G)") (class "Default")
      (node (ref "U$13") (pin "4") (pinfunction "G_4") (pintype "bidirectional"))
      (node (ref "U5") (pin "7") (pinfunction "HO_7") (pintype "output"))
    )
    (net (code "53") (name "Net-(U$14-G)") (class "Default")
      (node (ref "U$14") (pin "4") (pinfunction "G_4") (pintype "bidirectional"))
      (node (ref "U5") (pin "5") (pinfunction "LO_5") (pintype "output"))
    )
    (net (code "54") (name "Net-(U$16-G)") (class "Default")
      (node (ref "U$16") (pin "4") (pinfunction "G_4") (pintype "bidirectional"))
      (node (ref "U6") (pin "7") (pinfunction "HO_7") (pintype "output"))
    )
    (net (code "55") (name "Net-(U$17-G)") (class "Default")
      (node (ref "U$17") (pin "4") (pinfunction "G_4") (pintype "bidirectional"))
      (node (ref "U6") (pin "5") (pinfunction "LO_5") (pintype "output"))
    )
    (net (code "56") (name "Net-(U$19-G)") (class "Default")
      (node (ref "U$19") (pin "4") (pinfunction "G_4") (pintype "bidirectional"))
      (node (ref "U7") (pin "7") (pinfunction "HO_7") (pintype "output"))
    )
    (net (code "57") (name "Net-(U$20-G)") (class "Default")
      (node (ref "U$20") (pin "4") (pinfunction "G_4") (pintype "bidirectional"))
      (node (ref "U7") (pin "5") (pinfunction "LO_5") (pintype "output"))
    )
    (net (code "58") (name "Net-(U1A-PH1)") (class "Default")
      (node (ref "C1") (pin "1") (pinfunction "1_1") (pintype "passive"))
      (node (ref "Q1") (pin "1") (pinfunction "1_1") (pintype "passive"))
      (node (ref "U1") (pin "13") (pinfunction "PH1_13") (pintype "bidirectional"))
    )
    (net (code "59") (name "Net-(U1A-VCAP_1)") (class "Default")
      (node (ref "C4") (pin "1") (pinfunction "1_1") (pintype "passive"))
      (node (ref "U1") (pin "48") (pinfunction "VCAP_1_48") (pintype "power_in"))
    )
    (net (code "60") (name "Net-(U1B-VCAP_2)") (class "Default")
      (node (ref "C5") (pin "2") (pinfunction "2_2") (pintype "passive"))
      (node (ref "U1") (pin "73") (pinfunction "VCAP_2_73") (pintype "power_in"))
    )
    (net (code "61") (name "Net-(U2-HB)") (class "Default")
      (node (ref "C17") (pin "2") (pinfunction "2_2") (pintype "passive"))
      (node (ref "U2") (pin "8") (pinfunction "HB_8") (pintype "input"))
    )
    (net (code "62") (name "Net-(U2-HS)") (class "Default")
      (node (ref "C17") (pin "1") (pinfunction "1_1") (pintype "passive"))
      (node (ref "U$4") (pin "1") (pinfunction "S_1") (pintype "bidirectional"))
      (node (ref "U$4") (pin "2") (pinfunction "S_2") (pintype "bidirectional"))
      (node (ref "U$4") (pin "3") (pinfunction "S_3") (pintype "bidirectional"))
      (node (ref "U$5") (pin "5") (pinfunction "D_5") (pintype "bidirectional"))
      (node (ref "U$5") (pin "6") (pinfunction "D_6") (pintype "bidirectional"))
      (node (ref "U$5") (pin "7") (pinfunction "D_7") (pintype "bidirectional"))
      (node (ref "U$5") (pin "8") (pinfunction "D_8") (pintype "bidirectional"))
      (node (ref "U$6") (pin "P$1") (pinfunction "P$1_P$1") (pintype "bidirectional"))
      (node (ref "U2") (pin "6") (pinfunction "HS_6") (pintype "input"))
    )
    (net (code "63") (name "Net-(U3-HB)") (class "Default")
      (node (ref "C20") (pin "2") (pinfunction "2_2") (pintype "passive"))
      (node (ref "U3") (pin "8") (pinfunction "HB_8") (pintype "input"))
    )
    (net (code "64") (name "Net-(U3-HS)") (class "Default")
      (node (ref "C20") (pin "1") (pinfunction "1_1") (pintype "passive"))
      (node (ref "U$7") (pin "1") (pinfunction "S_1") (pintype "bidirectional"))
      (node (ref "U$7") (pin "2") (pinfunction "S_2") (pintype "bidirectional"))
      (node (ref "U$7") (pin "3") (pinfunction "S_3") (pintype "bidirectional"))
      (node (ref "U$8") (pin "5") (pinfunction "D_5") (pintype "bidirectional"))
      (node (ref "U$8") (pin "6") (pinfunction "D_6") (pintype "bidirectional"))
      (node (ref "U$8") (pin "7") (pinfunction "D_7") (pintype "bidirectional"))
      (node (ref "U$8") (pin "8") (pinfunction "D_8") (pintype "bidirectional"))
      (node (ref "U$9") (pin "P$1") (pinfunction "P$1_P$1") (pintype "bidirectional"))
      (node (ref "U3") (pin "6") (pinfunction "HS_6") (pintype "input"))
    )
    (net (code "65") (name "Net-(U4-HB)") (class "Default")
      (node (ref "C23") (pin "2") (pinfunction "2_2") (pintype "passive"))
      (node (ref "U4") (pin "8") (pinfunction "HB_8") (pintype "input"))
    )
    (net (code "66") (name "Net-(U4-HS)") (class "Default")
      (node (ref "C23") (pin "1") (pinfunction "1_1") (pintype "passive"))
      (node (ref "U$10") (pin "1") (pinfunction "S_1") (pintype "bidirectional"))
      (node (ref "U$10") (pin "2") (pinfunction "S_2") (pintype "bidirectional"))
      (node (ref "U$10") (pin "3") (pinfunction "S_3") (pintype "bidirectional"))
      (node (ref "U$11") (pin "5") (pinfunction "D_5") (pintype "bidirectional"))
      (node (ref "U$11") (pin "6") (pinfunction "D_6") (pintype "bidirectional"))
      (node (ref "U$11") (pin "7") (pinfunction "D_7") (pintype "bidirectional"))
      (node (ref "U$11") (pin "8") (pinfunction "D_8") (pintype "bidirectional"))
      (node (ref "U$12") (pin "P$1") (pinfunction "P$1_P$1") (pintype "bidirectional"))
      (node (ref "U4") (pin "6") (pinfunction "HS_6") (pintype "input"))
    )
    (net (code "67") (name "Net-(U5-HB)") (class "Default")
      (node (ref "C26") (pin "2") (pinfunction "2_2") (pintype "passive"))
      (node (ref "U5") (pin "8") (pinfunction "HB_8") (pintype "input"))
    )
    (net (code "68") (name "Net-(U5-HS)") (class "Default")
      (node (ref "C26") (pin "1") (pinfunction "1_1") (pintype "passive"))
      (node (ref "U$13") (pin "1") (pinfunction "S_1") (pintype "bidirectional"))
      (node (ref "U$13") (pin "2") (pinfunction "S_2") (pintype "bidirectional"))
      (node (ref "U$13") (pin "3") (pinfunction "S_3") (pintype "bidirectional"))
      (node (ref "U$14") (pin "5") (pinfunction "D_5") (pintype "bidirectional"))
      (node (ref "U$14") (pin "6") (pinfunction "D_6") (pintype "bidirectional"))
      (node (ref "U$14") (pin "7") (pinfunction "D_7") (pintype "bidirectional"))
      (node (ref "U$14") (pin "8") (pinfunction "D_8") (pintype "bidirectional"))
      (node (ref "U$15") (pin "P$1") (pinfunction "P$1_P$1") (pintype "bidirectional"))
      (node (ref "U5") (pin "6") (pinfunction "HS_6") (pintype "input"))
    )
    (net (code "69") (name "Net-(U6-HB)") (class "Default")
      (node (ref "C29") (pin "2") (pinfunction "2_2") (pintype "passive"))
      (node (ref "U6") (pin "8") (pinfunction "HB_8") (pintype "input"))
    )
    (net (code "70") (name "Net-(U6-HS)") (class "Default")
      (node (ref "C29") (pin "1") (pinfunction "1_1") (pintype "passive"))
      (node (ref "U$16") (pin "1") (pinfunction "S_1") (pintype "bidirectional"))
      (node (ref "U$16") (pin "2") (pinfunction "S_2") (pintype "bidirectional"))
      (node (ref "U$16") (pin "3") (pinfunction "S_3") (pintype "bidirectional"))
      (node (ref "U$17") (pin "5") (pinfunction "D_5") (pintype "bidirectional"))
      (node (ref "U$17") (pin "6") (pinfunction "D_6") (pintype "bidirectional"))
      (node (ref "U$17") (pin "7") (pinfunction "D_7") (pintype "bidirectional"))
      (node (ref "U$17") (pin "8") (pinfunction "D_8") (pintype "bidirectional"))
      (node (ref "U$18") (pin "P$1") (pinfunction "P$1_P$1") (pintype "bidirectional"))
      (node (ref "U6") (pin "6") (pinfunction "HS_6") (pintype "input"))
    )
    (net (code "71") (name "Net-(U7-HB)") (class "Default")
      (node (ref "C32") (pin "2") (pinfunction "2_2") (pintype "passive"))
      (node (ref "U7") (pin "8") (pinfunction "HB_8") (pintype "input"))
    )
    (net (code "72") (name "Net-(U7-HS)") (class "Default")
      (node (ref "C32") (pin "1") (pinfunction "1_1") (pintype "passive"))
      (node (ref "U$19") (pin "1") (pinfunction "S_1") (pintype "bidirectional"))
      (node (ref "U$19") (pin "2") (pinfunction "S_2") (pintype "bidirectional"))
      (node (ref "U$19") (pin "3") (pinfunction "S_3") (pintype "bidirectional"))
      (node (ref "U$20") (pin "5") (pinfunction "D_5") (pintype "bidirectional"))
      (node (ref "U$20") (pin "6") (pinfunction "D_6") (pintype "bidirectional"))
      (node (ref "U$20") (pin "7") (pinfunction "D_7") (pintype "bidirectional"))
      (node (ref "U$20") (pin "8") (pinfunction "D_8") (pintype "bidirectional"))
      (node (ref "U$21") (pin "P$1") (pinfunction "P$1_P$1") (pintype "bidirectional"))
      (node (ref "U7") (pin "6") (pinfunction "HS_6") (pintype "input"))
    )
    (net (code "73") (name "VCC") (class "Default")
      (node (ref "C18") (pin "1") (pinfunction "1_1") (pintype "passive"))
      (node (ref "C19") (pin "1") (pinfunction "1_1") (pintype "passive"))
      (node (ref "C21") (pin "1") (pinfunction "1_1") (pintype "passive"))
      (node (ref "C22") (pin "1") (pinfunction "1_1") (pintype "passive"))
      (node (ref "C24") (pin "1") (pinfunction "1_1") (pintype "passive"))
      (node (ref "C25") (pin "1") (pinfunction "1_1") (pintype "passive"))
      (node (ref "C27") (pin "1") (pinfunction "1_1") (pintype "passive"))
      (node (ref "C28") (pin "1") (pinfunction "1_1") (pintype "passive"))
      (node (ref "C30") (pin "1") (pinfunction "1_1") (pintype "passive"))
      (node (ref "C31") (pin "1") (pinfunction "1_1") (pintype "passive"))
      (node (ref "C33") (pin "1") (pinfunction "1_1") (pintype "passive"))
      (node (ref "C34") (pin "1") (pinfunction "1_1") (pintype "passive"))
      (node (ref "U$10") (pin "5") (pinfunction "D_5") (pintype "bidirectional"))
      (node (ref "U$10") (pin "6") (pinfunction "D_6") (pintype "bidirectional"))
      (node (ref "U$10") (pin "7") (pinfunction "D_7") (pintype "bidirectional"))
      (node (ref "U$10") (pin "8") (pinfunction "D_8") (pintype "bidirectional"))
      (node (ref "U$13") (pin "5") (pinfunction "D_5") (pintype "bidirectional"))
      (node (ref "U$13") (pin "6") (pinfunction "D_6") (pintype "bidirectional"))
      (node (ref "U$13") (pin "7") (pinfunction "D_7") (pintype "bidirectional"))
      (node (ref "U$13") (pin "8") (pinfunction "D_8") (pintype "bidirectional"))
      (node (ref "U$16") (pin "5") (pinfunction "D_5") (pintype "bidirectional"))
      (node (ref "U$16") (pin "6") (pinfunction "D_6") (pintype "bidirectional"))
      (node (ref "U$16") (pin "7") (pinfunction "D_7") (pintype "bidirectional"))
      (node (ref "U$16") (pin "8") (pinfunction "D_8") (pintype "bidirectional"))
      (node (ref "U$19") (pin "5") (pinfunction "D_5") (pintype "bidirectional"))
      (node (ref "U$19") (pin "6") (pinfunction "D_6") (pintype "bidirectional"))
      (node (ref "U$19") (pin "7") (pinfunction "D_7") (pintype "bidirectional"))
      (node (ref "U$19") (pin "8") (pinfunction "D_8") (pintype "bidirectional"))
      (node (ref "U$4") (pin "5") (pinfunction "D_5") (pintype "bidirectional"))
      (node (ref "U$4") (pin "6") (pinfunction "D_6") (pintype "bidirectional"))
      (node (ref "U$4") (pin "7") (pinfunction "D_7") (pintype "bidirectional"))
      (node (ref "U$4") (pin "8") (pinfunction "D_8") (pintype "bidirectional"))
      (node (ref "U$7") (pin "5") (pinfunction "D_5") (pintype "bidirectional"))
      (node (ref "U$7") (pin "6") (pinfunction "D_6") (pintype "bidirectional"))
      (node (ref "U$7") (pin "7") (pinfunction "D_7") (pintype "bidirectional"))
      (node (ref "U$7") (pin "8") (pinfunction "D_8") (pintype "bidirectional"))
      (node (ref "U2") (pin "1") (pinfunction "VDD_1") (pintype "power_in"))
      (node (ref "U3") (pin "1") (pinfunction "VDD_1") (pintype "power_in"))
      (node (ref "U4") (pin "1") (pinfunction "VDD_1") (pintype "power_in"))
      (node (ref "U5") (pin "1") (pinfunction "VDD_1") (pintype "power_in"))
      (node (ref "U6") (pin "1") (pinfunction "VDD_1") (pintype "power_in"))
      (node (ref "U7") (pin "1") (pinfunction "VDD_1") (pintype "power_in"))
    )
    (net (code "74") (name "unconnected-(RESET-Pad2)") (class "Default")
      (node (ref "RESET") (pin "2") (pinfunction "2_2") (pintype "passive"))
    )
    (net (code "75") (name "unconnected-(RESET-Pad4)") (class "Default")
      (node (ref "RESET") (pin "4") (pinfunction "4_4") (pintype "passive"))
    )
    (net (code "76") (name "unconnected-(U$1-NC-PadP$4)") (class "Default")
      (node (ref "U$1") (pin "P$4") (pinfunction "NC_P$4") (pintype "bidirectional"))
    )
    (net (code "77") (name "unconnected-(U$2-DRDY{slash}INT2-PadP$6)") (class "Default")
      (node (ref "U$2") (pin "P$6") (pinfunction "DRDY/INT2_P$6") (pintype "bidirectional"))
    )
    (net (code "78") (name "unconnected-(U$2-INT1-PadP$7)") (class "Default")
      (node (ref "U$2") (pin "P$7") (pinfunction "INT1_P$7") (pintype "bidirectional"))
    )
    (net (code "79") (name "unconnected-(U$22-ALERT-PadP$5)") (class "Default")
      (node (ref "U$22") (pin "P$5") (pinfunction "ALERT_P$5") (pintype "bidirectional"))
    )
    (net (code "80") (name "unconnected-(U$23-ALERT-PadP$5)") (class "Default")
      (node (ref "U$23") (pin "P$5") (pinfunction "ALERT_P$5") (pintype "bidirectional"))
    )
    (net (code "81") (name "unconnected-(U$24-ALERT-PadP$5)") (class "Default")
      (node (ref "U$24") (pin "P$5") (pinfunction "ALERT_P$5") (pintype "bidirectional"))
    )
    (net (code "82") (name "unconnected-(U$25-ALERT-PadP$5)") (class "Default")
      (node (ref "U$25") (pin "P$5") (pinfunction "ALERT_P$5") (pintype "bidirectional"))
    )
    (net (code "83") (name "unconnected-(U1A-PC0-Pad15)") (class "Default")
      (node (ref "U1") (pin "15") (pinfunction "PC0_15") (pintype "bidirectional"))
    )
    (net (code "84") (name "unconnected-(U1A-PC1-Pad16)") (class "Default")
      (node (ref "U1") (pin "16") (pinfunction "PC1_16") (pintype "bidirectional"))
    )
    (net (code "85") (name "unconnected-(U1A-PC2-Pad17)") (class "Default")
      (node (ref "U1") (pin "17") (pinfunction "PC2_17") (pintype "bidirectional"))
    )
    (net (code "86") (name "unconnected-(U1A-PC3-Pad18)") (class "Default")
      (node (ref "U1") (pin "18") (pinfunction "PC3_18") (pintype "bidirectional"))
    )
    (net (code "87") (name "unconnected-(U1A-PC4-Pad32)") (class "Default")
      (node (ref "U1") (pin "32") (pinfunction "PC4_32") (pintype "bidirectional"))
    )
    (net (code "88") (name "unconnected-(U1A-PC5-Pad33)") (class "Default")
      (node (ref "U1") (pin "33") (pinfunction "PC5_33") (pintype "bidirectional"))
    )
    (net (code "89") (name "unconnected-(U1A-PC13-Pad7)") (class "Default")
      (node (ref "U1") (pin "7") (pinfunction "PC13_7") (pintype "bidirectional"))
    )
    (net (code "90") (name "unconnected-(U1A-PC14-Pad8)") (class "Default")
      (node (ref "U1") (pin "8") (pinfunction "PC14_8") (pintype "bidirectional"))
    )
    (net (code "91") (name "unconnected-(U1A-PC15-Pad9)") (class "Default")
      (node (ref "U1") (pin "9") (pinfunction "PC15_9") (pintype "bidirectional"))
    )
    (net (code "92") (name "unconnected-(U1B-PA13-Pad72)") (class "Default")
      (node (ref "U1") (pin "72") (pinfunction "PA13_72") (pintype "bidirectional"))
    )
    (net (code "93") (name "unconnected-(U1B-PA14-Pad76)") (class "Default")
      (node (ref "U1") (pin "76") (pinfunction "PA14_76") (pintype "bidirectional"))
    )
    (net (code "94") (name "unconnected-(U1B-PA15-Pad77)") (class "Default")
      (node (ref "U1") (pin "77") (pinfunction "PA15_77") (pintype "bidirectional"))
    )
    (net (code "95") (name "unconnected-(U1B-PB3-Pad89)") (class "Default")
      (node (ref "U1") (pin "89") (pinfunction "PB3_89") (pintype "bidirectional"))
    )
    (net (code "96") (name "unconnected-(U1B-PB4-Pad90)") (class "Default")
      (node (ref "U1") (pin "90") (pinfunction "PB4_90") (pintype "bidirectional"))
    )
    (net (code "97") (name "unconnected-(U1B-PB5-Pad91)") (class "Default")
      (node (ref "U1") (pin "91") (pinfunction "PB5_91") (pintype "bidirectional"))
    )
    (net (code "98") (name "unconnected-(U1B-PB8-Pad95)") (class "Default")
      (node (ref "U1") (pin "95") (pinfunction "PB8_95") (pintype "bidirectional"))
    )
    (net (code "99") (name "unconnected-(U1B-PB9-Pad96)") (class "Default")
      (node (ref "U1") (pin "96") (pinfunction "PB9_96") (pintype "bidirectional"))
    )
    (net (code "100") (name "unconnected-(U1B-PB12-Pad51)") (class "Default")
      (node (ref "U1") (pin "51") (pinfunction "PB12_51") (pintype "bidirectional"))
    )
    (net (code "101") (name "unconnected-(U1B-PB13-Pad52)") (class "Default")
      (node (ref "U1") (pin "52") (pinfunction "PB13_52") (pintype "bidirectional"))
    )
    (net (code "102") (name "unconnected-(U1B-PB14-Pad53)") (class "Default")
      (node (ref "U1") (pin "53") (pinfunction "PB14_53") (pintype "bidirectional"))
    )
    (net (code "103") (name "unconnected-(U1B-PB15-Pad54)") (class "Default")
      (node (ref "U1") (pin "54") (pinfunction "PB15_54") (pintype "bidirectional"))
    )
    (net (code "104") (name "unconnected-(U1B-PC6-Pad63)") (class "Default")
      (node (ref "U1") (pin "63") (pinfunction "PC6_63") (pintype "bidirectional"))
    )
    (net (code "105") (name "unconnected-(U1B-PC7-Pad64)") (class "Default")
      (node (ref "U1") (pin "64") (pinfunction "PC7_64") (pintype "bidirectional"))
    )
    (net (code "106") (name "unconnected-(U1B-PC8-Pad65)") (class "Default")
      (node (ref "U1") (pin "65") (pinfunction "PC8_65") (pintype "bidirectional"))
    )
    (net (code "107") (name "unconnected-(U1B-PC10-Pad78)") (class "Default")
      (node (ref "U1") (pin "78") (pinfunction "PC10_78") (pintype "bidirectional"))
    )
    (net (code "108") (name "unconnected-(U1B-PC11-Pad79)") (class "Default")
      (node (ref "U1") (pin "79") (pinfunction "PC11_79") (pintype "bidirectional"))
    )
    (net (code "109") (name "unconnected-(U1B-PC12-Pad80)") (class "Default")
      (node (ref "U1") (pin "80") (pinfunction "PC12_80") (pintype "bidirectional"))
    )
    (net (code "110") (name "unconnected-(U1B-PD0-Pad81)") (class "Default")
      (node (ref "U1") (pin "81") (pinfunction "PD0_81") (pintype "bidirectional"))
    )
    (net (code "111") (name "unconnected-(U1B-PD1-Pad82)") (class "Default")
      (node (ref "U1") (pin "82") (pinfunction "PD1_82") (pintype "bidirectional"))
    )
    (net (code "112") (name "unconnected-(U1B-PD2-Pad83)") (class "Default")
      (node (ref "U1") (pin "83") (pinfunction "PD2_83") (pintype "bidirectional"))
    )
    (net (code "113") (name "unconnected-(U1B-PD3-Pad84)") (class "Default")
      (node (ref "U1") (pin "84") (pinfunction "PD3_84") (pintype "bidirectional"))
    )
    (net (code "114") (name "unconnected-(U1B-PD4-Pad85)") (class "Default")
      (node (ref "U1") (pin "85") (pinfunction "PD4_85") (pintype "bidirectional"))
    )
    (net (code "115") (name "unconnected-(U1B-PD5-Pad86)") (class "Default")
      (node (ref "U1") (pin "86") (pinfunction "PD5_86") (pintype "bidirectional"))
    )
    (net (code "116") (name "unconnected-(U1B-PD6-Pad87)") (class "Default")
      (node (ref "U1") (pin "87") (pinfunction "PD6_87") (pintype "bidirectional"))
    )
    (net (code "117") (name "unconnected-(U1B-PD7-Pad88)") (class "Default")
      (node (ref "U1") (pin "88") (pinfunction "PD7_88") (pintype "bidirectional"))
    )
    (net (code "118") (name "unconnected-(U1B-PD8-Pad55)") (class "Default")
      (node (ref "U1") (pin "55") (pinfunction "PD8_55") (pintype "bidirectional"))
    )
    (net (code "119") (name "unconnected-(U1B-PD9-Pad56)") (class "Default")
      (node (ref "U1") (pin "56") (pinfunction "PD9_56") (pintype "bidirectional"))
    )
    (net (code "120") (name "unconnected-(U1B-PD10-Pad57)") (class "Default")
      (node (ref "U1") (pin "57") (pinfunction "PD10_57") (pintype "bidirectional"))
    )
    (net (code "121") (name "unconnected-(U1B-PD11-Pad58)") (class "Default")
      (node (ref "U1") (pin "58") (pinfunction "PD11_58") (pintype "bidirectional"))
    )
    (net (code "122") (name "unconnected-(U1B-PD12-Pad59)") (class "Default")
      (node (ref "U1") (pin "59") (pinfunction "PD12_59") (pintype "bidirectional"))
    )
    (net (code "123") (name "unconnected-(U1B-PD13-Pad60)") (class "Default")
      (node (ref "U1") (pin "60") (pinfunction "PD13_60") (pintype "bidirectional"))
    )
    (net (code "124") (name "unconnected-(U1B-PD14-Pad61)") (class "Default")
      (node (ref "U1") (pin "61") (pinfunction "PD14_61") (pintype "bidirectional"))
    )
    (net (code "125") (name "unconnected-(U1B-PD15-Pad62)") (class "Default")
      (node (ref "U1") (pin "62") (pinfunction "PD15_62") (pintype "bidirectional"))
    )
    (net (code "126") (name "unconnected-(U1B-PE0-Pad97)") (class "Default")
      (node (ref "U1") (pin "97") (pinfunction "PE0_97") (pintype "bidirectional"))
    )
    (net (code "127") (name "unconnected-(U1B-PE1-Pad98)") (class "Default")
      (node (ref "U1") (pin "98") (pinfunction "PE1_98") (pintype "bidirectional"))
    )
    (net (code "128") (name "unconnected-(X1-Pad4)") (class "Default")
      (node (ref "X1") (pin "4") (pinfunction "4_4") (pintype "passive"))
    )
    (net (code "129") (name "unconnected-(X2A-S-Pad1)") (class "Default")
      (node (ref "X2") (pin "1") (pinfunction "S_1") (pintype "passive"))
    )
    (net (code "130") (name "unconnected-(X2B-S-Pad10)") (class "Default")
      (node (ref "X2") (pin "10") (pinfunction "S_10") (pintype "passive"))
    )
    (net (code "131") (name "unconnected-(X2C-S-Pad11)") (class "Default")
      (node (ref "X2") (pin "11") (pinfunction "S_11") (pintype "passive"))
    )
    (net (code "132") (name "unconnected-(X2D-S-Pad12)") (class "Default")
      (node (ref "X2") (pin "12") (pinfunction "S_12") (pintype "passive"))
    )
    (net (code "133") (name "unconnected-(X2E-S-Pad13)") (class "Default")
      (node (ref "X2") (pin "13") (pinfunction "S_13") (pintype "passive"))
    )
    (net (code "134") (name "unconnected-(X2F-S-Pad14)") (class "Default")
      (node (ref "X2") (pin "14") (pinfunction "S_14") (pintype "passive"))
    )
    (net (code "135") (name "unconnected-(X2G-S-Pad15)") (class "Default")
      (node (ref "X2") (pin "15") (pinfunction "S_15") (pintype "passive"))
    )
    (net (code "136") (name "unconnected-(X2H-S-Pad16)") (class "Default")
      (node (ref "X2") (pin "16") (pinfunction "S_16") (pintype "passive"))
    )
    (net (code "137") (name "unconnected-(X2I-S-Pad17)") (class "Default")
      (node (ref "X2") (pin "17") (pinfunction "S_17") (pintype "passive"))
    )
    (net (code "138") (name "unconnected-(X2J-S-Pad18)") (class "Default")
      (node (ref "X2") (pin "18") (pinfunction "S_18") (pintype "passive"))
    )
    (net (code "139") (name "unconnected-(X2K-S-Pad2)") (class "Default")
      (node (ref "X2") (pin "2") (pinfunction "S_2") (pintype "passive"))
    )
    (net (code "140") (name "unconnected-(X2L-S-Pad3)") (class "Default")
      (node (ref "X2") (pin "3") (pinfunction "S_3") (pintype "passive"))
    )
    (net (code "141") (name "unconnected-(X2M-S-Pad4)") (class "Default")
      (node (ref "X2") (pin "4") (pinfunction "S_4") (pintype "passive"))
    )
    (net (code "142") (name "unconnected-(X2N-S-Pad5)") (class "Default")
      (node (ref "X2") (pin "5") (pinfunction "S_5") (pintype "passive"))
    )
    (net (code "143") (name "unconnected-(X2O-S-Pad6)") (class "Default")
      (node (ref "X2") (pin "6") (pinfunction "S_6") (pintype "passive"))
    )
    (net (code "144") (name "unconnected-(X2P-S-Pad7)") (class "Default")
      (node (ref "X2") (pin "7") (pinfunction "S_7") (pintype "passive"))
    )
    (net (code "145") (name "unconnected-(X2Q-S-Pad8)") (class "Default")
      (node (ref "X2") (pin "8") (pinfunction "S_8") (pintype "passive"))
    )
    (net (code "146") (name "unconnected-(X2R-S-Pad9)") (class "Default")
      (node (ref "X2") (pin "9") (pinfunction "S_9") (pintype "passive"))
    )
  )
)
